# controller-ic.net
KiCad netlist of a schematic drawn in Altium Designer
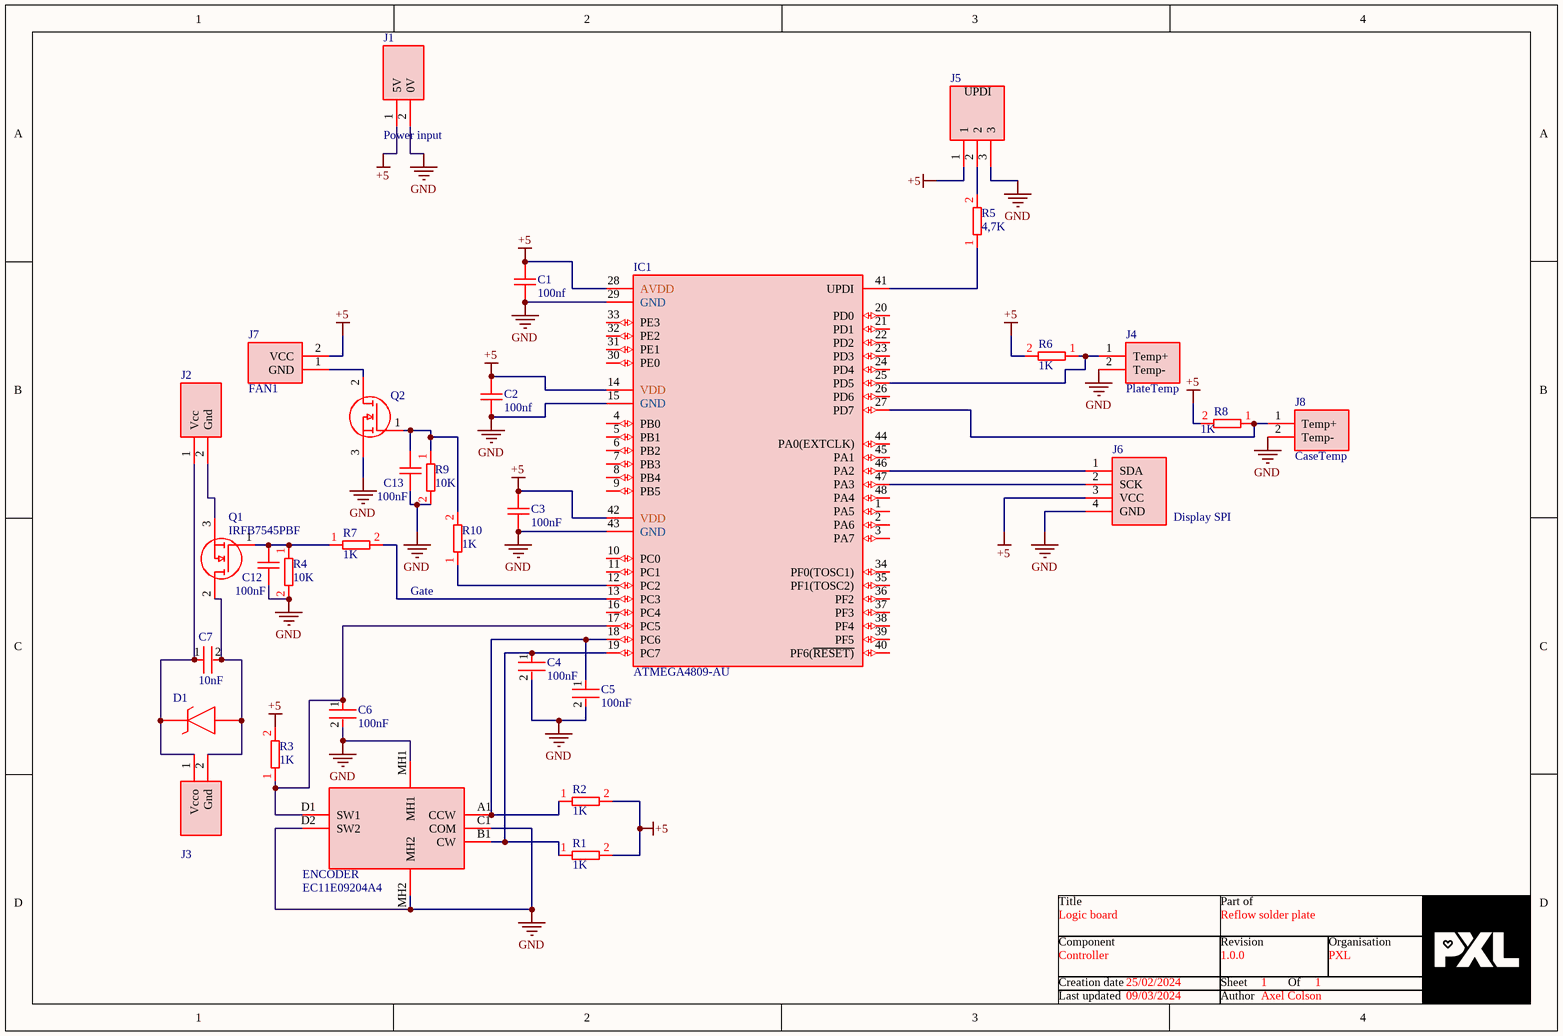
[diagram p0: controller-ic.SchDoc]

(export (version "E")
  (design (tool "Eeschema 10.0.6"))
  (components
    (comp (ref "C1")
      (value "100nf")
      (footprint "CAP_0603US-IPC_C")
      (fields
        (field (name "MANUFACTURER") "AVX Interconnect / Elco")
        (field (name "PART NUMBER") "08051C103JAT2A")
      )
      (libsource (lib "SolderIron") (part "D_Capacitor_0805CC"))
    )
    (comp (ref "C2")
      (value "100nf")
      (footprint "CAP_0603US-IPC_C")
      (fields
        (field (name "MANUFACTURER") "AVX Interconnect / Elco")
        (field (name "PART NUMBER") "08051C103JAT2A")
      )
      (libsource (lib "SolderIron") (part "D_Capacitor_0805CC"))
    )
    (comp (ref "C3")
      (value "100nF")
      (footprint "CAP_0603US-IPC_C")
      (fields
        (field (name "MANUFACTURER") "AVX Interconnect / Elco")
        (field (name "PART NUMBER") "08051C103JAT2A")
      )
      (libsource (lib "SolderIron") (part "D_Capacitor_0805CC"))
    )
    (comp (ref "C4")
      (value "100nF")
      (footprint "CAP_0603US-IPC_C")
      (description "CAP CER 0.1UF 25V X7R 0603")
      (fields (field (name "TOLERANCE") "10%"))
      (libsource (lib "SolderIron") (part "D_Capacitor_0603CC"))
    )
    (comp (ref "C5")
      (value "100nF")
      (footprint "CAP_0603US-IPC_C")
      (description "CAP CER 0.1UF 25V X7R 0603")
      (fields (field (name "TOLERANCE") "10%"))
      (libsource (lib "SolderIron") (part "D_Capacitor_0603CC"))
    )
    (comp (ref "C6")
      (value "100nF")
      (footprint "CAP_0603US-IPC_C")
      (description "CAP CER 0.1UF 25V X7R 0603")
      (fields (field (name "TOLERANCE") "10%"))
      (libsource (lib "SolderIron") (part "D_Capacitor_0603CC"))
    )
    (comp (ref "C7")
      (value "10nF")
      (footprint "CAP_0603US-IPC_C")
      (description "CAP CER 0.1UF 25V X7R 0603")
      (fields (field (name "TOLERANCE") "10%"))
      (libsource (lib "SolderIron") (part "D_Capacitor_0603CC"))
    )
    (comp (ref "C12")
      (value "100nF")
      (footprint "CAP_0603US-IPC_C")
      (fields
        (field (name "MANUFACTURER") "AVX Interconnect / Elco")
        (field (name "PART NUMBER") "08051C103JAT2A")
      )
      (libsource (lib "SolderIron") (part "D_Capacitor_0805CC"))
    )
    (comp (ref "C13")
      (value "100nF")
      (footprint "CAP_0603US-IPC_C")
      (fields
        (field (name "MANUFACTURER") "AVX Interconnect / Elco")
        (field (name "PART NUMBER") "08051C103JAT2A")
      )
      (libsource (lib "SolderIron") (part "D_Capacitor_0805CC"))
    )
    (comp (ref "D1")
      (value "ZENER_TH")
      (footprint "ZENER_SMF_DO219AB")
      (libsource (lib "SolderIron") (part "ZENER_TH"))
    )
    (comp (ref "ENCODER")
      (value "EC11E09204A4")
      (footprint "ENC_ROT_EC11")
      (fields (field (name "MOUSER PART NUMBER") "688-EC11E09204A4"))
      (libsource (lib "SolderIron") (part "ENC_ROTEC11E09"))
    )
    (comp (ref "IC1")
      (value "ATMEGA4809-AU")
      (footprint "IC_ATmega4809AF-IPC_A")
      (description "MCU 8-BIT")
      (libsource (lib "SolderIron") (part "IC_ATMega4809"))
    )
    (comp (ref "J1")
      (value "Power input")
      (footprint "CON_M1x2PIN_SHROUDED")
      (description "Connector")
      (fields (field (name "MANUFACTURER_PART_NUMBER") "SMC-1-02-1-GT"))
      (libsource (lib "SolderIron") (part "CON_F1x3Pin"))
    )
    (comp (ref "J2")
      (value "CON_F1x2Pin")
      (footprint "CON_M1x2PIN_SHROUDED")
      (description "Connector")
      (fields (field (name "MANUFACTURER_PART_NUMBER") "SMC-1-02-1-GT"))
      (libsource (lib "") (part "CON_F1x2Pin_1"))
    )
    (comp (ref "J3")
      (value "CON_F1x2Pin")
      (footprint "CON_M1x2PIN_SHROUDED")
      (description "Gated signal")
      (fields (field (name "MANUFACTURER_PART_NUMBER") "SMC-1-02-1-GT"))
      (libsource (lib "") (part "CON_F1x2Pin_3"))
    )
    (comp (ref "J4")
      (value "PlateTemp")
      (footprint "CON_M1x2PIN_SHROUDED")
      (description "Connector")
      (fields (field (name "MANUFACTURER_PART_NUMBER") "SMC-1-02-1-GT"))
      (libsource (lib "SolderIron") (part "CON_F1x2Pin"))
    )
    (comp (ref "J5")
      (value "890-70-003-10-001101")
      (footprint "CON_M1x3PIN")
      (description "Headers & Wire Housings")
      (fields (field (name "USE") "UPDI"))
      (libsource (lib "SolderIron") (part "CON_3pin"))
    )
    (comp (ref "J6")
      (value "CON_M1x4Pin")
      (footprint "CON_M1x4PIN_Shrouded")
      (libsource (lib "SolderIron") (part "CON_M1x4Pin"))
    )
    (comp (ref "J7")
      (value "FAN1")
      (footprint "CON_M1X2PIN_CLAMP")
      (description "Connector")
      (fields (field (name "MANUFACTURER_PART_NUMBER") "SMC-1-02-1-GT"))
      (libsource (lib "") (part "CON_F1x2Pin_2"))
    )
    (comp (ref "J8")
      (value "CaseTemp")
      (footprint "CON_M1X2PIN_CLAMP")
      (description "Connector")
      (fields (field (name "MANUFACTURER_PART_NUMBER") "SMC-1-02-1-GT"))
      (libsource (lib "SolderIron") (part "CON_F1x2Pin"))
    )
    (comp (ref "Q1")
      (value "IRFB7545PBF")
      (footprint "MOSFET_TO254P483X1016X1994")
      (description "IRFB7545PBF N-Channel MOSFET, 95 A, 60 V StrongIRFET, 3-Pin TO-220AB Infineon")
      (fields (field (name "MOUSER PART NUMBER") "942-IRFB7545PBF"))
      (libsource (lib "SolderIron") (part "MOSFET_IRFB745PBF"))
    )
    (comp (ref "Q2")
      (value "IRFB7545PBF")
      (footprint "MOSFET_SOT23_MMFTN6001")
      (description "IRFB7545PBF N-Channel MOSFET, 95 A, 60 V StrongIRFET, 3-Pin TO-220AB Infineon")
      (fields (field (name "MOUSER PART NUMBER") "942-IRFB7545PBF"))
      (libsource (lib "SolderIron") (part "MOSFET_IRFB745PBF"))
    )
    (comp (ref "R1")
      (value "1K")
      (footprint "RES_0603US_TF-IPC_C")
      (description "SMD 0603 Thick Film 4.7kΩ 5.00% 0.1W")
      (fields (field (name "TOLERANCE") "5%"))
      (libsource (lib "SolderIron") (part "D_Resistor_TF0603"))
    )
    (comp (ref "R2")
      (value "1K")
      (footprint "RES_0603US_TF-IPC_C")
      (description "SMD 0603 Thick Film 4.7kΩ 5.00% 0.1W")
      (fields (field (name "TOLERANCE") "5%"))
      (libsource (lib "SolderIron") (part "D_Resistor_TF0603"))
    )
    (comp (ref "R3")
      (value "1K")
      (footprint "RES_0603US_TF-IPC_C")
      (description "SMD 0603 Thick Film 4.7kΩ 5.00% 0.1W")
      (fields (field (name "TOLERANCE") "5%"))
      (libsource (lib "") (part "D_Resistor_TF0603_3"))
    )
    (comp (ref "R4")
      (value "10K")
      (footprint "RES_0603US_TF-IPC_C")
      (description "SMD 0603 Thick Film 4.7kΩ 5.00% 0.1W")
      (fields (field (name "TOLERANCE") "5%"))
      (libsource (lib "") (part "D_Resistor_TF0603_1"))
    )
    (comp (ref "R5")
      (value "4,7K")
      (footprint "RES_0603US_TF-IPC_C")
      (description "SMD 0603 Thick Film 4.7kΩ 5.00% 0.1W")
      (fields (field (name "TOLERANCE") "5%"))
      (libsource (lib "") (part "D_Resistor_TF0603_3"))
    )
    (comp (ref "R6")
      (value "1K")
      (footprint "RES_0603US_TF-IPC_C")
      (description "SMD 0603 Thick Film 4.7kΩ 5.00% 0.1W")
      (fields (field (name "TOLERANCE") "5%"))
      (libsource (lib "") (part "D_Resistor_TF0603_2"))
    )
    (comp (ref "R7")
      (value "1K")
      (footprint "RES_0603US_TF-IPC_C")
      (description "SMD 0603 Thick Film 4.7kΩ 5.00% 0.1W")
      (fields (field (name "TOLERANCE") "5%"))
      (libsource (lib "SolderIron") (part "D_Resistor_TF0603"))
    )
    (comp (ref "R8")
      (value "1K")
      (footprint "RES_0603US_TF-IPC_C")
      (description "SMD 0603 Thick Film 4.7kΩ 5.00% 0.1W")
      (fields (field (name "TOLERANCE") "5%"))
      (libsource (lib "") (part "D_Resistor_TF0603_2"))
    )
    (comp (ref "R9")
      (value "10K")
      (footprint "RES_0603US_TF-IPC_C")
      (description "SMD 0603 Thick Film 4.7kΩ 5.00% 0.1W")
      (fields (field (name "TOLERANCE") "5%"))
      (libsource (lib "") (part "D_Resistor_TF0603_1"))
    )
    (comp (ref "R10")
      (value "1K")
      (footprint "RES_0603US_TF-IPC_C")
      (description "SMD 0603 Thick Film 4.7kΩ 5.00% 0.1W")
      (fields (field (name "TOLERANCE") "5%"))
      (libsource (lib "") (part "D_Resistor_TF0603_3"))
    )
  )
  (nets
    (net (code "1") (name "+5") (class "Default")
      (node (ref "C1") (pin "2") (pinfunction "2_2") (pintype "passive"))
      (node (ref "C2") (pin "2") (pinfunction "2_2") (pintype "passive"))
      (node (ref "C3") (pin "2") (pinfunction "2_2") (pintype "passive"))
      (node (ref "IC1") (pin "14") (pinfunction "VDD_14") (pintype "power_in"))
      (node (ref "IC1") (pin "28") (pinfunction "AVDD_28") (pintype "power_in"))
      (node (ref "IC1") (pin "42") (pinfunction "VDD_42") (pintype "power_in"))
      (node (ref "J1") (pin "1") (pinfunction "5V_1") (pintype "passive"))
      (node (ref "J5") (pin "1") (pinfunction "1_1") (pintype "passive"))
      (node (ref "J6") (pin "3") (pinfunction "VCC_3") (pintype "passive"))
      (node (ref "J7") (pin "2") (pinfunction "VCC_2") (pintype "passive"))
      (node (ref "R1") (pin "2") (pinfunction "2_2") (pintype "passive"))
      (node (ref "R2") (pin "2") (pinfunction "2_2") (pintype "passive"))
      (node (ref "R3") (pin "2") (pinfunction "2_2") (pintype "passive"))
      (node (ref "R6") (pin "2") (pinfunction "2_2") (pintype "passive"))
      (node (ref "R8") (pin "2") (pinfunction "2_2") (pintype "passive"))
    )
    (net (code "2") (name "GND") (class "Default")
      (node (ref "C1") (pin "1") (pinfunction "1_1") (pintype "passive"))
      (node (ref "C12") (pin "1") (pinfunction "1_1") (pintype "passive"))
      (node (ref "C13") (pin "1") (pinfunction "1_1") (pintype "passive"))
      (node (ref "C2") (pin "1") (pinfunction "1_1") (pintype "passive"))
      (node (ref "C3") (pin "1") (pinfunction "1_1") (pintype "passive"))
      (node (ref "C4") (pin "2") (pinfunction "2_2") (pintype "passive"))
      (node (ref "C5") (pin "2") (pinfunction "2_2") (pintype "passive"))
      (node (ref "C6") (pin "2") (pinfunction "2_2") (pintype "passive"))
      (node (ref "ENCODER") (pin "C1") (pinfunction "COM_C1") (pintype "passive"))
      (node (ref "ENCODER") (pin "D2") (pinfunction "SW2_D2") (pintype "passive"))
      (node (ref "ENCODER") (pin "MH1") (pinfunction "MH1_MH1") (pintype "passive"))
      (node (ref "ENCODER") (pin "MH2") (pinfunction "MH2_MH2") (pintype "passive"))
      (node (ref "IC1") (pin "15") (pinfunction "GND_15") (pintype "passive"))
      (node (ref "IC1") (pin "29") (pinfunction "GND_29") (pintype "passive"))
      (node (ref "IC1") (pin "43") (pinfunction "GND_43") (pintype "passive"))
      (node (ref "J1") (pin "2") (pinfunction "0V_2") (pintype "passive"))
      (node (ref "J4") (pin "2") (pinfunction "Temp-_2") (pintype "passive"))
      (node (ref "J5") (pin "3") (pinfunction "3_3") (pintype "passive"))
      (node (ref "J6") (pin "4") (pinfunction "GND_4") (pintype "passive"))
      (node (ref "J8") (pin "2") (pinfunction "Temp-_2") (pintype "passive"))
      (node (ref "Q2") (pin "3") (pinfunction "S_3") (pintype "passive"))
      (node (ref "R4") (pin "2") (pinfunction "2_2") (pintype "passive"))
      (node (ref "R9") (pin "2") (pinfunction "2_2") (pintype "passive"))
    )
    (net (code "3") (name "Net-(D1-A)") (class "Default")
      (node (ref "C7") (pin "2") (pinfunction "2_2") (pintype "passive"))
      (node (ref "D1") (pin "2") (pinfunction "A_2") (pintype "passive"))
      (node (ref "J3") (pin "2") (pinfunction "Gnd_2") (pintype "passive"))
      (node (ref "Q1") (pin "2") (pinfunction "D_2") (pintype "passive"))
    )
    (net (code "4") (name "Net-(D1-K)") (class "Default")
      (node (ref "C7") (pin "1") (pinfunction "1_1") (pintype "passive"))
      (node (ref "D1") (pin "1") (pinfunction "K_1") (pintype "passive"))
      (node (ref "J2") (pin "1") (pinfunction "Vcc_1") (pintype "passive"))
      (node (ref "J3") (pin "1") (pinfunction "Vcco_1") (pintype "passive"))
    )
    (net (code "5") (name "Net-(ENCODER-CCW)") (class "Default")
      (node (ref "C5") (pin "1") (pinfunction "1_1") (pintype "passive"))
      (node (ref "ENCODER") (pin "A1") (pinfunction "CCW_A1") (pintype "passive"))
      (node (ref "IC1") (pin "18") (pinfunction "PC6_18") (pintype "bidirectional"))
      (node (ref "R2") (pin "1") (pinfunction "1_1") (pintype "passive"))
    )
    (net (code "6") (name "Net-(ENCODER-CW)") (class "Default")
      (node (ref "C4") (pin "1") (pinfunction "1_1") (pintype "passive"))
      (node (ref "ENCODER") (pin "B1") (pinfunction "CW_B1") (pintype "passive"))
      (node (ref "IC1") (pin "19") (pinfunction "PC7_19") (pintype "bidirectional"))
      (node (ref "R1") (pin "1") (pinfunction "1_1") (pintype "passive"))
    )
    (net (code "7") (name "Net-(ENCODER-SW1)") (class "Default")
      (node (ref "C6") (pin "1") (pinfunction "1_1") (pintype "passive"))
      (node (ref "ENCODER") (pin "D1") (pinfunction "SW1_D1") (pintype "passive"))
      (node (ref "IC1") (pin "17") (pinfunction "PC5_17") (pintype "bidirectional"))
      (node (ref "R3") (pin "1") (pinfunction "1_1") (pintype "passive"))
    )
    (net (code "8") (name "Net-(IC1-PA2)") (class "Default")
      (node (ref "IC1") (pin "46") (pinfunction "PA2_46") (pintype "bidirectional"))
      (node (ref "J6") (pin "1") (pinfunction "SDA_1") (pintype "passive"))
    )
    (net (code "9") (name "Net-(IC1-PA3)") (class "Default")
      (node (ref "IC1") (pin "47") (pinfunction "PA3_47") (pintype "bidirectional"))
      (node (ref "J6") (pin "2") (pinfunction "SCK_2") (pintype "passive"))
    )
    (net (code "10") (name "Net-(IC1-PC2)") (class "Default")
      (node (ref "IC1") (pin "12") (pinfunction "PC2_12") (pintype "bidirectional"))
      (node (ref "R10") (pin "1") (pinfunction "1_1") (pintype "passive"))
    )
    (net (code "11") (name "Net-(IC1-PC3)") (class "Default")
      (node (ref "IC1") (pin "13") (pinfunction "PC3_13") (pintype "bidirectional"))
      (node (ref "R7") (pin "2") (pinfunction "2_2") (pintype "passive"))
    )
    (net (code "12") (name "Net-(IC1-PD5)") (class "Default")
      (node (ref "IC1") (pin "25") (pinfunction "PD5_25") (pintype "bidirectional"))
      (node (ref "J4") (pin "1") (pinfunction "Temp+_1") (pintype "passive"))
      (node (ref "R6") (pin "1") (pinfunction "1_1") (pintype "passive"))
    )
    (net (code "13") (name "Net-(IC1-PD7)") (class "Default")
      (node (ref "IC1") (pin "27") (pinfunction "PD7_27") (pintype "bidirectional"))
      (node (ref "J8") (pin "1") (pinfunction "Temp+_1") (pintype "passive"))
      (node (ref "R8") (pin "1") (pinfunction "1_1") (pintype "passive"))
    )
    (net (code "14") (name "Net-(IC1-UPDI)") (class "Default")
      (node (ref "IC1") (pin "41") (pinfunction "UPDI_41") (pintype "passive"))
      (node (ref "R5") (pin "1") (pinfunction "1_1") (pintype "passive"))
    )
    (net (code "15") (name "Net-(J2-Gnd)") (class "Default")
      (node (ref "J2") (pin "2") (pinfunction "Gnd_2") (pintype "passive"))
      (node (ref "Q1") (pin "3") (pinfunction "S_3") (pintype "passive"))
    )
    (net (code "16") (name "Net-(J5-Pad2)") (class "Default")
      (node (ref "J5") (pin "2") (pinfunction "2_2") (pintype "passive"))
      (node (ref "R5") (pin "2") (pinfunction "2_2") (pintype "passive"))
    )
    (net (code "17") (name "Net-(J7-GND)") (class "Default")
      (node (ref "J7") (pin "1") (pinfunction "GND_1") (pintype "passive"))
      (node (ref "Q2") (pin "2") (pinfunction "D_2") (pintype "passive"))
    )
    (net (code "18") (name "Net-(Q1-G)") (class "Default")
      (node (ref "C12") (pin "2") (pinfunction "2_2") (pintype "passive"))
      (node (ref "Q1") (pin "1") (pinfunction "G_1") (pintype "passive"))
      (node (ref "R4") (pin "1") (pinfunction "1_1") (pintype "passive"))
      (node (ref "R7") (pin "1") (pinfunction "1_1") (pintype "passive"))
    )
    (net (code "19") (name "Net-(Q2-G)") (class "Default")
      (node (ref "C13") (pin "2") (pinfunction "2_2") (pintype "passive"))
      (node (ref "Q2") (pin "1") (pinfunction "G_1") (pintype "passive"))
      (node (ref "R10") (pin "2") (pinfunction "2_2") (pintype "passive"))
      (node (ref "R9") (pin "1") (pinfunction "1_1") (pintype "passive"))
    )
    (net (code "20") (name "unconnected-(IC1-PA0(EXTCLK)-Pad44)") (class "Default")
      (node (ref "IC1") (pin "44") (pinfunction "PA0(EXTCLK)_44") (pintype "bidirectional"))
    )
    (net (code "21") (name "unconnected-(IC1-PA1-Pad45)") (class "Default")
      (node (ref "IC1") (pin "45") (pinfunction "PA1_45") (pintype "bidirectional"))
    )
    (net (code "22") (name "unconnected-(IC1-PA4-Pad48)") (class "Default")
      (node (ref "IC1") (pin "48") (pinfunction "PA4_48") (pintype "bidirectional"))
    )
    (net (code "23") (name "unconnected-(IC1-PA5-Pad1)") (class "Default")
      (node (ref "IC1") (pin "1") (pinfunction "PA5_1") (pintype "bidirectional"))
    )
    (net (code "24") (name "unconnected-(IC1-PA6-Pad2)") (class "Default")
      (node (ref "IC1") (pin "2") (pinfunction "PA6_2") (pintype "bidirectional"))
    )
    (net (code "25") (name "unconnected-(IC1-PA7-Pad3)") (class "Default")
      (node (ref "IC1") (pin "3") (pinfunction "PA7_3") (pintype "bidirectional"))
    )
    (net (code "26") (name "unconnected-(IC1-PB0-Pad4)") (class "Default")
      (node (ref "IC1") (pin "4") (pinfunction "PB0_4") (pintype "bidirectional"))
    )
    (net (code "27") (name "unconnected-(IC1-PB1-Pad5)") (class "Default")
      (node (ref "IC1") (pin "5") (pinfunction "PB1_5") (pintype "bidirectional"))
    )
    (net (code "28") (name "unconnected-(IC1-PB2-Pad6)") (class "Default")
      (node (ref "IC1") (pin "6") (pinfunction "PB2_6") (pintype "bidirectional"))
    )
    (net (code "29") (name "unconnected-(IC1-PB3-Pad7)") (class "Default")
      (node (ref "IC1") (pin "7") (pinfunction "PB3_7") (pintype "bidirectional"))
    )
    (net (code "30") (name "unconnected-(IC1-PB4-Pad8)") (class "Default")
      (node (ref "IC1") (pin "8") (pinfunction "PB4_8") (pintype "bidirectional"))
    )
    (net (code "31") (name "unconnected-(IC1-PB5-Pad9)") (class "Default")
      (node (ref "IC1") (pin "9") (pinfunction "PB5_9") (pintype "bidirectional"))
    )
    (net (code "32") (name "unconnected-(IC1-PC0-Pad10)") (class "Default")
      (node (ref "IC1") (pin "10") (pinfunction "PC0_10") (pintype "bidirectional"))
    )
    (net (code "33") (name "unconnected-(IC1-PC1-Pad11)") (class "Default")
      (node (ref "IC1") (pin "11") (pinfunction "PC1_11") (pintype "bidirectional"))
    )
    (net (code "34") (name "unconnected-(IC1-PC4-Pad16)") (class "Default")
      (node (ref "IC1") (pin "16") (pinfunction "PC4_16") (pintype "bidirectional"))
    )
    (net (code "35") (name "unconnected-(IC1-PD0-Pad20)") (class "Default")
      (node (ref "IC1") (pin "20") (pinfunction "PD0_20") (pintype "bidirectional"))
    )
    (net (code "36") (name "unconnected-(IC1-PD1-Pad21)") (class "Default")
      (node (ref "IC1") (pin "21") (pinfunction "PD1_21") (pintype "bidirectional"))
    )
    (net (code "37") (name "unconnected-(IC1-PD2-Pad22)") (class "Default")
      (node (ref "IC1") (pin "22") (pinfunction "PD2_22") (pintype "bidirectional"))
    )
    (net (code "38") (name "unconnected-(IC1-PD3-Pad23)") (class "Default")
      (node (ref "IC1") (pin "23") (pinfunction "PD3_23") (pintype "bidirectional"))
    )
    (net (code "39") (name "unconnected-(IC1-PD4-Pad24)") (class "Default")
      (node (ref "IC1") (pin "24") (pinfunction "PD4_24") (pintype "bidirectional"))
    )
    (net (code "40") (name "unconnected-(IC1-PD6-Pad26)") (class "Default")
      (node (ref "IC1") (pin "26") (pinfunction "PD6_26") (pintype "bidirectional"))
    )
    (net (code "41") (name "unconnected-(IC1-PE0-Pad30)") (class "Default")
      (node (ref "IC1") (pin "30") (pinfunction "PE0_30") (pintype "bidirectional"))
    )
    (net (code "42") (name "unconnected-(IC1-PE1-Pad31)") (class "Default")
      (node (ref "IC1") (pin "31") (pinfunction "PE1_31") (pintype "bidirectional"))
    )
    (net (code "43") (name "unconnected-(IC1-PE2-Pad32)") (class "Default")
      (node (ref "IC1") (pin "32") (pinfunction "PE2_32") (pintype "bidirectional"))
    )
    (net (code "44") (name "unconnected-(IC1-PE3-Pad33)") (class "Default")
      (node (ref "IC1") (pin "33") (pinfunction "PE3_33") (pintype "bidirectional"))
    )
    (net (code "45") (name "unconnected-(IC1-PF0(TOSC1)-Pad34)") (class "Default")
      (node (ref "IC1") (pin "34") (pinfunction "PF0(TOSC1)_34") (pintype "bidirectional"))
    )
    (net (code "46") (name "unconnected-(IC1-PF1(TOSC2)-Pad35)") (class "Default")
      (node (ref "IC1") (pin "35") (pinfunction "PF1(TOSC2)_35") (pintype "bidirectional"))
    )
    (net (code "47") (name "unconnected-(IC1-PF2-Pad36)") (class "Default")
      (node (ref "IC1") (pin "36") (pinfunction "PF2_36") (pintype "bidirectional"))
    )
    (net (code "48") (name "unconnected-(IC1-PF3-Pad37)") (class "Default")
      (node (ref "IC1") (pin "37") (pinfunction "PF3_37") (pintype "bidirectional"))
    )
    (net (code "49") (name "unconnected-(IC1-PF4-Pad38)") (class "Default")
      (node (ref "IC1") (pin "38") (pinfunction "PF4_38") (pintype "bidirectional"))
    )
    (net (code "50") (name "unconnected-(IC1-PF5-Pad39)") (class "Default")
      (node (ref "IC1") (pin "39") (pinfunction "PF5_39") (pintype "bidirectional"))
    )
    (net (code "51") (name "unconnected-(IC1-PF6(~{RESET)}-Pad40)") (class "Default")
      (node (ref "IC1") (pin "40") (pinfunction "PF6(~{RESET)}_40") (pintype "bidirectional"))
    )
  )
)
